# Power.net
KiCad netlist of a schematic drawn in Altium Designer
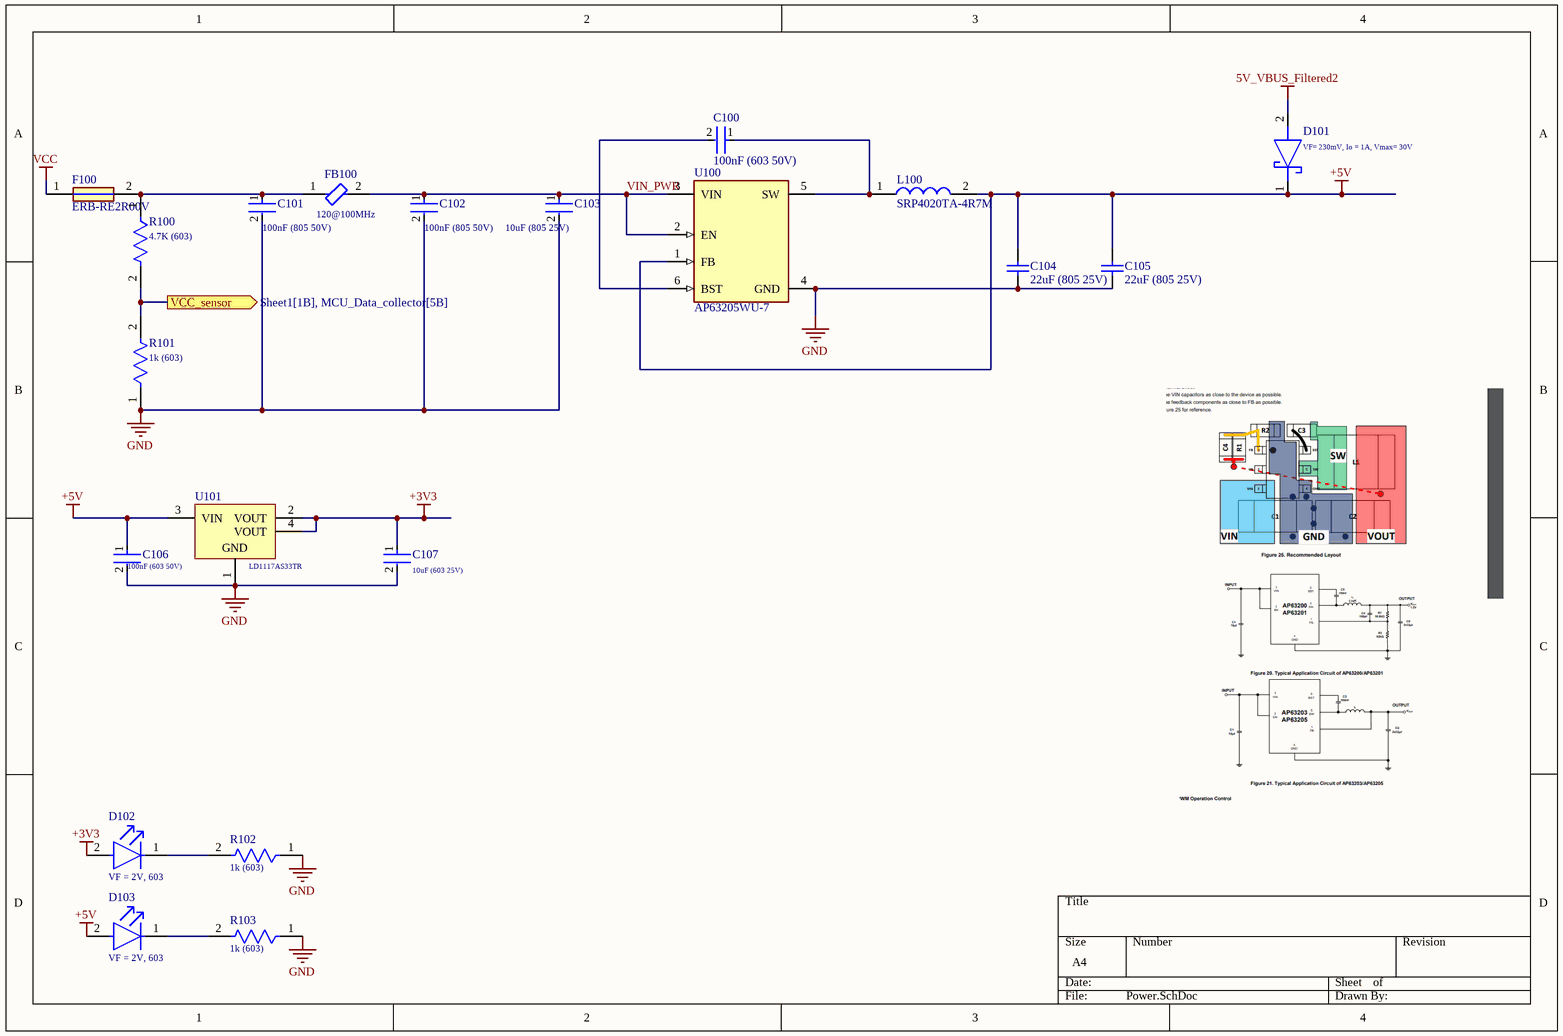
[diagram p0: Power.SchDoc]

(export (version "E")
  (design (tool "Eeschema 10.0.6"))
  (components
    (comp (ref "C100")
      (value "100nF (603 50V)")
      (footprint "FP-CC0603-DA-MFG")
      (description "CAP CER 0.1UF 50V X7R 0603")
      (fields (field (name "MANUFACTURER") "YAGEO") (field (name "VOLTAGE") "50 V"))
      (libsource (lib "Altium Content Vault") (part "11868f565c42a9108669ba33697ecf6"))
    )
    (comp (ref "C101")
      (value "100nF (805 50V)")
      (footprint "FP-CL779-IPC_C")
      (description "Cap Ceramic 100nF 50V X7R ±10% SMD 0402 +125°C Paper T/R")
      (libsource (lib "Altium Content Vault") (part "b4654b650e69147ec39a6b967a45e02"))
    )
    (comp (ref "C102")
      (value "100nF (805 50V)")
      (footprint "FP-CL779-IPC_C")
      (description "Cap Ceramic 100nF 50V X7R ±10% SMD 0402 +125°C Paper T/R")
      (libsource (lib "Altium Content Vault") (part "b4654b650e69147ec39a6b967a45e02"))
    )
    (comp (ref "C103")
      (value "10uF (805 25V)")
      (footprint "FP-CL21-IPC_A")
      (description "CL21 Series 0805 10uF 25V ±10% Tolerance X5R Multilayer Ceramic Chip Capacitor")
      (fields (field (name "TOLERANCE") "10%"))
      (libsource (lib "Altium Content Vault") (part "b4654b650e69147ec39a6b967a45e02"))
    )
    (comp (ref "C104")
      (value "22uF (805 25V)")
      (footprint "CAPC2013X140X45LL15T25")
      (description "Multi-layer Ceramic Capacitor, 22 uF, -55 to 85 degC, 2-Pin SMD (0805), RoHS, Tape and Reel")
      (fields (field (name "MANUFACTURER") "Samsung Electro-Mechanics") (field (name "TOLERANCE") "±20%"))
      (libsource (lib "Altium Content Vault") (part "CAP-NP-2"))
    )
    (comp (ref "C105")
      (value "22uF (805 25V)")
      (footprint "CAPC2013X140X45LL15T25")
      (description "Multi-layer Ceramic Capacitor, 22 uF, -55 to 85 degC, 2-Pin SMD (0805), RoHS, Tape and Reel")
      (fields (field (name "MANUFACTURER") "Samsung Electro-Mechanics") (field (name "TOLERANCE") "±20%"))
      (libsource (lib "Altium Content Vault") (part "CAP-NP-2"))
    )
    (comp (ref "C106")
      (value "100nF (603 50V)")
      (footprint "FP-CC0603-DA-MFG")
      (description "CAP CER 0.1UF 50V X7R 0603")
      (fields (field (name "MANUFACTURER") "YAGEO") (field (name "VOLTAGE") "50 V"))
      (libsource (lib "Altium Content Vault") (part "11868f565c42a9108669ba33697ecf6"))
    )
    (comp (ref "C107")
      (value "10uF (603 25V)")
      (footprint "FP-CL10-IPC_C")
      (description "Cap Ceramic 10uF 25V X5R ±20% Pad SMD 0603 +85°C T/R")
      (fields (field (name "TOLERANCE") "20%"))
      (libsource (lib "Altium Content Vault") (part "b4654b650e69147ec39a6b967a45e02"))
    )
    (comp (ref "D101")
      (value "VF= 230mV, Io = 1A, Vmax= 30V")
      (footprint "SamacSys:1SS357TPH3F")
      (description "Schottky Diode")
      (fields
        (field (name "MANUFACTURER_PART_NUMBER") "CUS10S30,H3F")
        (field (name "MOUSER PART NUMBER") "757-CUS10S30H3F")
      )
      (libsource (lib "*") (part "CUS10S30,H3F"))
    )
    (comp (ref "D102")
      (value "VF = 2V, 603")
      (footprint "FP-LTST-C191KGKT-MFG")
      (description "LED GREEN CLEAR SMD")
      (libsource (lib "Altium Content Vault") (part "8706943c75ba83719d021d2fdc84c58"))
    )
    (comp (ref "D103")
      (value "VF = 2V, 603")
      (footprint "FP-LTST-C191KGKT-MFG")
      (description "LED GREEN CLEAR SMD")
      (libsource (lib "Altium Content Vault") (part "8706943c75ba83719d021d2fdc84c58"))
    )
    (comp (ref "F100")
      (value "ERB-RE2R00V")
      (footprint "SamacSys:ERBRE0R50V")
      (description "Fuse")
      (fields (field (name "MOUSER PART NUMBER") "667-ERB-RE2R00V"))
      (libsource (lib "*") (part "ERB-RE2R00V"))
    )
    (comp (ref "FB100")
      (value "120@100MHz")
      (footprint "FP-BLM18-0_15-t0_8-MFG")
      (description "Chip Ferrite Bead, 0603, 120Ω @ 100MHz, 0.25Ω, 25%, 200mA")
      (fields (field (name "TOLERANCE") "25%"))
      (libsource (lib "Altium Content Vault") (part "5f30dd21d616792df468990f7003faa"))
    )
    (comp (ref "L100")
      (value "SRP4020TA-4R7M")
      (footprint "SamacSys:INDPM4441X200N")
      (description "Inductor")
      (fields (field (name "MOUSER PART NUMBER") "652-SRP4020TA-4R7M"))
      (libsource (lib "*") (part "SRP4020TA-4R7M"))
    )
    (comp (ref "R100")
      (value "4.7K (603)")
      (footprint "FP-CRCW0603-e3-IPC_A")
      (description "RES Thick Film, 4.7kΩ, 1%, 0.1W, 100ppm/°C, 0603")
      (fields (field (name "TOLERANCE") "1%"))
      (libsource (lib "Altium Content Vault") (part "1029c3af85768c4190bb7ad29bc67b5"))
    )
    (comp (ref "R101")
      (value "1k (603)")
      (footprint "FP-CRCW0603-e3-MFG")
      (description "RES Thick Film, 1kΩ, 1%, 0.1W, 100ppm/°C, 0603")
      (fields (field (name "TOLERANCE") "1%"))
      (libsource (lib "Altium Content Vault") (part "1029c3af85768c4190bb7ad29bc67b5"))
    )
    (comp (ref "R102")
      (value "1k (603)")
      (footprint "FP-CRCW0603-e3-MFG")
      (description "RES Thick Film, 1kΩ, 1%, 0.1W, 100ppm/°C, 0603")
      (fields (field (name "TOLERANCE") "1%"))
      (libsource (lib "Altium Content Vault") (part "1029c3af85768c4190bb7ad29bc67b5"))
    )
    (comp (ref "R103")
      (value "1k (603)")
      (footprint "FP-CRCW0603-e3-MFG")
      (description "RES Thick Film, 1kΩ, 1%, 0.1W, 100ppm/°C, 0603")
      (fields (field (name "TOLERANCE") "1%"))
      (libsource (lib "Altium Content Vault") (part "1029c3af85768c4190bb7ad29bc67b5"))
    )
    (comp (ref "U100")
      (value "AP63205WU-7")
      (footprint "FP-TSOT26-MFG")
      (description "IC REG BUCK 5V 2A TSOT26")
      (fields
        (field (name "MANUFACTURER") "Diodes Inc.")
        (field (name "OCTOPART") "https://octopart.com/ap63205wu-7-diodes+inc.-98099551")
      )
      (libsource (lib "Altium Content Vault") (part "029bc9fbfa4a99dbb8b3a24c2adb655"))
    )
    (comp (ref "U101")
      (value "LD1117AS33TR")
      (footprint "SOT-223_M")
      (description "1A, Low Drop Positive Voltage Regulator, 3.3V, 4-Pin SOT-223, Tape and Reel")
      (libsource (lib "Altium Content Vault") (part "PM-REG-LD1117-SOT4"))
    )
  )
  (nets
    (net (code "1") (name "+3V3") (class "Default")
      (node (ref "C107") (pin "1") (pinfunction "1_1") (pintype "passive"))
      (node (ref "D102") (pin "2") (pinfunction "A_2") (pintype "passive"))
      (node (ref "U101") (pin "2") (pinfunction "VOUT_2") (pintype "power_in"))
      (node (ref "U101") (pin "4") (pinfunction "VOUT_4") (pintype "power_in"))
    )
    (net (code "2") (name "+5V") (class "Default")
      (node (ref "C104") (pin "2") (pinfunction "2_2") (pintype "passive"))
      (node (ref "C105") (pin "2") (pinfunction "2_2") (pintype "passive"))
      (node (ref "C106") (pin "1") (pinfunction "1_1") (pintype "passive"))
      (node (ref "D101") (pin "1") (pinfunction "K_1") (pintype "passive"))
      (node (ref "D103") (pin "2") (pinfunction "A_2") (pintype "passive"))
      (node (ref "L100") (pin "2") (pinfunction "2_2") (pintype "passive"))
      (node (ref "U100") (pin "1") (pinfunction "FB_1") (pintype "input"))
      (node (ref "U101") (pin "3") (pinfunction "VIN_3") (pintype "power_in"))
    )
    (net (code "3") (name "/VCC_sensor") (class "Default")
      (node (ref "R100") (pin "2") (pinfunction "2_2") (pintype "passive"))
      (node (ref "R101") (pin "2") (pinfunction "2_2") (pintype "passive"))
    )
    (net (code "4") (name "/VIN_PWR") (class "Default")
      (node (ref "C102") (pin "1") (pinfunction "1_1") (pintype "passive"))
      (node (ref "C103") (pin "1") (pinfunction "1_1") (pintype "passive"))
      (node (ref "FB100") (pin "2") (pinfunction "2_2") (pintype "passive"))
      (node (ref "U100") (pin "2") (pinfunction "EN_2") (pintype "input"))
      (node (ref "U100") (pin "3") (pinfunction "VIN_3") (pintype "power_in"))
    )
    (net (code "5") (name "5V_VBUS_Filtered2") (class "Default")
      (node (ref "D101") (pin "2") (pinfunction "A_2") (pintype "passive"))
    )
    (net (code "6") (name "GND") (class "Default")
      (node (ref "C101") (pin "2") (pinfunction "2_2") (pintype "passive"))
      (node (ref "C102") (pin "2") (pinfunction "2_2") (pintype "passive"))
      (node (ref "C103") (pin "2") (pinfunction "2_2") (pintype "passive"))
      (node (ref "C104") (pin "1") (pinfunction "1_1") (pintype "passive"))
      (node (ref "C105") (pin "1") (pinfunction "1_1") (pintype "passive"))
      (node (ref "C106") (pin "2") (pinfunction "2_2") (pintype "passive"))
      (node (ref "C107") (pin "2") (pinfunction "2_2") (pintype "passive"))
      (node (ref "R101") (pin "1") (pinfunction "1_1") (pintype "passive"))
      (node (ref "R102") (pin "1") (pinfunction "1_1") (pintype "passive"))
      (node (ref "R103") (pin "1") (pinfunction "1_1") (pintype "passive"))
      (node (ref "U100") (pin "4") (pinfunction "GND_4") (pintype "power_in"))
      (node (ref "U101") (pin "1") (pinfunction "GND_1") (pintype "power_in"))
    )
    (net (code "7") (name "Net-(C101-Pad1)") (class "Default")
      (node (ref "C101") (pin "1") (pinfunction "1_1") (pintype "passive"))
      (node (ref "F100") (pin "2") (pinfunction "2_2") (pintype "passive"))
      (node (ref "FB100") (pin "1") (pinfunction "1_1") (pintype "passive"))
      (node (ref "R100") (pin "1") (pinfunction "1_1") (pintype "passive"))
    )
    (net (code "8") (name "Net-(D102-C)") (class "Default")
      (node (ref "D102") (pin "1") (pinfunction "C_1") (pintype "passive"))
      (node (ref "R102") (pin "2") (pinfunction "2_2") (pintype "passive"))
    )
    (net (code "9") (name "Net-(D103-C)") (class "Default")
      (node (ref "D103") (pin "1") (pinfunction "C_1") (pintype "passive"))
      (node (ref "R103") (pin "2") (pinfunction "2_2") (pintype "passive"))
    )
    (net (code "10") (name "Net-(U100-BST)") (class "Default")
      (node (ref "C100") (pin "2") (pinfunction "2_2") (pintype "passive"))
      (node (ref "U100") (pin "6") (pinfunction "BST_6") (pintype "input"))
    )
    (net (code "11") (name "Net-(U100-SW)") (class "Default")
      (node (ref "C100") (pin "1") (pinfunction "1_1") (pintype "passive"))
      (node (ref "L100") (pin "1") (pinfunction "1_1") (pintype "passive"))
      (node (ref "U100") (pin "5") (pinfunction "SW_5") (pintype "power_in"))
    )
    (net (code "12") (name "VCC") (class "Default")
      (node (ref "F100") (pin "1") (pinfunction "1_1") (pintype "passive"))
    )
  )
)
